# bmb_extender.net
KiCad netlist of a schematic drawn in Altium Designer
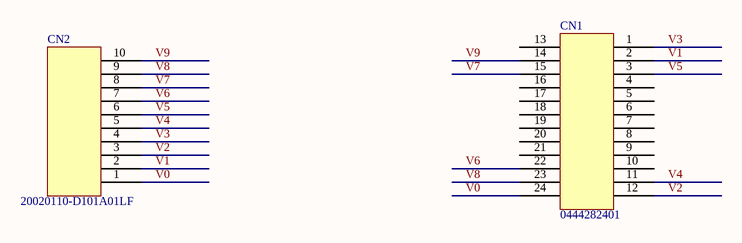
[diagram p0: bmb_extender.SchDoc]

(export (version "E")
  (design (tool "Eeschema 10.0.6"))
  (components
    (comp (ref "CN1")
      (value "0444282401")
      (footprint "MOLEX_0444282401")
      (libsource (lib "bmb_extender") (part "0444282401"))
    )
    (comp (ref "CN2") (value "20020110-D101A01LF") (libsource (lib "bmb_extender") (part "SIL10")))
  )
  (nets
    (net (code "1") (name "/V0") (class "Default")
      (node (ref "CN1") (pin "24") (pintype "passive"))
      (node (ref "CN2") (pin "1") (pintype "passive"))
    )
    (net (code "2") (name "/V1") (class "Default")
      (node (ref "CN1") (pin "2") (pintype "passive"))
      (node (ref "CN2") (pin "2") (pintype "passive"))
    )
    (net (code "3") (name "/V2") (class "Default")
      (node (ref "CN1") (pin "12") (pintype "passive"))
      (node (ref "CN2") (pin "3") (pintype "passive"))
    )
    (net (code "4") (name "/V3") (class "Default")
      (node (ref "CN1") (pin "1") (pintype "passive"))
      (node (ref "CN2") (pin "4") (pintype "passive"))
    )
    (net (code "5") (name "/V4") (class "Default")
      (node (ref "CN1") (pin "11") (pintype "passive"))
      (node (ref "CN2") (pin "5") (pintype "passive"))
    )
    (net (code "6") (name "/V5") (class "Default")
      (node (ref "CN1") (pin "3") (pintype "passive"))
      (node (ref "CN2") (pin "6") (pintype "passive"))
    )
    (net (code "7") (name "/V6") (class "Default")
      (node (ref "CN1") (pin "22") (pintype "passive"))
      (node (ref "CN2") (pin "7") (pintype "passive"))
    )
    (net (code "8") (name "/V7") (class "Default")
      (node (ref "CN1") (pin "15") (pintype "passive"))
      (node (ref "CN2") (pin "8") (pintype "passive"))
    )
    (net (code "9") (name "/V8") (class "Default")
      (node (ref "CN1") (pin "23") (pintype "passive"))
      (node (ref "CN2") (pin "9") (pintype "passive"))
    )
    (net (code "10") (name "/V9") (class "Default")
      (node (ref "CN1") (pin "14") (pintype "passive"))
      (node (ref "CN2") (pin "10") (pintype "passive"))
    )
    (net (code "11") (name "unconnected-(CN1-Pad4)") (class "Default")
      (node (ref "CN1") (pin "4") (pintype "passive"))
    )
    (net (code "12") (name "unconnected-(CN1-Pad5)") (class "Default")
      (node (ref "CN1") (pin "5") (pintype "passive"))
    )
    (net (code "13") (name "unconnected-(CN1-Pad6)") (class "Default")
      (node (ref "CN1") (pin "6") (pintype "passive"))
    )
    (net (code "14") (name "unconnected-(CN1-Pad7)") (class "Default")
      (node (ref "CN1") (pin "7") (pintype "passive"))
    )
    (net (code "15") (name "unconnected-(CN1-Pad8)") (class "Default")
      (node (ref "CN1") (pin "8") (pintype "passive"))
    )
    (net (code "16") (name "unconnected-(CN1-Pad9)") (class "Default")
      (node (ref "CN1") (pin "9") (pintype "passive"))
    )
    (net (code "17") (name "unconnected-(CN1-Pad10)") (class "Default")
      (node (ref "CN1") (pin "10") (pintype "passive"))
    )
    (net (code "18") (name "unconnected-(CN1-Pad13)") (class "Default")
      (node (ref "CN1") (pin "13") (pintype "passive"))
    )
    (net (code "19") (name "unconnected-(CN1-Pad16)") (class "Default")
      (node (ref "CN1") (pin "16") (pintype "passive"))
    )
    (net (code "20") (name "unconnected-(CN1-Pad17)") (class "Default")
      (node (ref "CN1") (pin "17") (pintype "passive"))
    )
    (net (code "21") (name "unconnected-(CN1-Pad18)") (class "Default")
      (node (ref "CN1") (pin "18") (pintype "passive"))
    )
    (net (code "22") (name "unconnected-(CN1-Pad19)") (class "Default")
      (node (ref "CN1") (pin "19") (pintype "passive"))
    )
    (net (code "23") (name "unconnected-(CN1-Pad20)") (class "Default")
      (node (ref "CN1") (pin "20") (pintype "passive"))
    )
    (net (code "24") (name "unconnected-(CN1-Pad21)") (class "Default")
      (node (ref "CN1") (pin "21") (pintype "passive"))
    )
  )
)
